# photodiodeAmplifier.net
KiCad netlist of a schematic drawn in Altium Designer
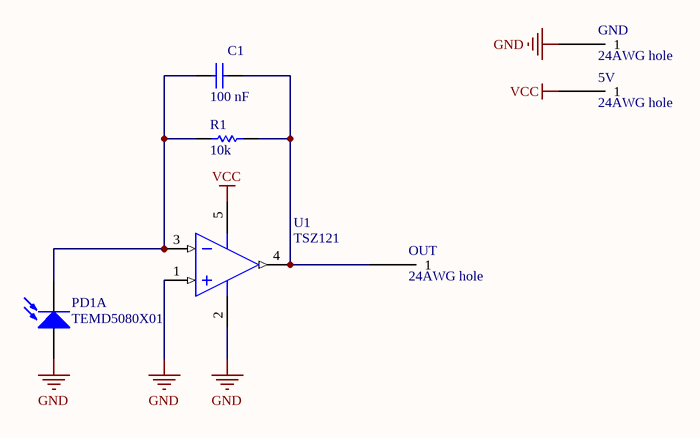
[diagram p0: photodiodeAmplifier.SchDoc]

(export (version "E")
  (design (tool "Eeschema 10.0.6"))
  (components
    (comp (ref "5V")
      (value "24AWG hole")
      (footprint "24AWG hole")
      (libsource (lib "AcqBoxLib") (part "24AWG hole"))
    )
    (comp (ref "C1") (value "100 nF") (footprint "CAP 0805") (libsource (lib "AcqBoxLib") (part "CAP 0805")))
    (comp (ref "GND")
      (value "24AWG hole")
      (footprint "24AWG hole")
      (libsource (lib "AcqBoxLib") (part "24AWG hole"))
    )
    (comp (ref "OUT")
      (value "24AWG hole")
      (footprint "24AWG hole")
      (libsource (lib "AcqBoxLib") (part "24AWG hole"))
    )
    (comp (ref "PD1")
      (value "TEMD5080X01")
      (footprint "Photodiode SMD PKG-1")
      (description "PIN Sillicium photodiode.")
      (libsource (lib "neigeMegaShieldLibrary") (part "TEMD5080X01"))
    )
    (comp (ref "R1")
      (value "10k")
      (footprint "RES 0805")
      (description "SMD Resistor 0805")
      (fields (field (name "Comment") "RES 0805"))
      (libsource (lib "AcqBoxLib") (part "RES 0805"))
    )
    (comp (ref "U1") (value "TSZ121") (footprint "SC-70-5") (libsource (lib "AcqBoxLib") (part "TSZ121")))
  )
  (nets
    (net (code "1") (name "GND") (class "Default")
      (node (ref "GND") (pin "1") (pinfunction "1_1") (pintype "passive"))
      (node (ref "PD1") (pin "1") (pinfunction "1_1") (pintype "passive"))
      (node (ref "U1") (pin "1") (pinfunction "INA+_1") (pintype "input"))
      (node (ref "U1") (pin "2") (pinfunction "V-_2") (pintype "power_in"))
    )
    (net (code "2") (name "Net-(U1-INA-)") (class "Default")
      (node (ref "C1") (pin "1") (pinfunction "1_1") (pintype "passive"))
      (node (ref "PD1") (pin "2") (pinfunction "2_2") (pintype "passive"))
      (node (ref "R1") (pin "1") (pinfunction "1_1") (pintype "passive"))
      (node (ref "U1") (pin "3") (pinfunction "INA-_3") (pintype "input"))
    )
    (net (code "3") (name "Net-(U1-OUTA)") (class "Default")
      (node (ref "C1") (pin "2") (pinfunction "2_2") (pintype "passive"))
      (node (ref "OUT") (pin "1") (pinfunction "1_1") (pintype "passive"))
      (node (ref "R1") (pin "2") (pinfunction "2_2") (pintype "passive"))
      (node (ref "U1") (pin "4") (pinfunction "OUTA_4") (pintype "output"))
    )
    (net (code "4") (name "VCC") (class "Default")
      (node (ref "5V") (pin "1") (pinfunction "1_1") (pintype "passive"))
      (node (ref "U1") (pin "5") (pinfunction "V+_5") (pintype "power_in"))
    )
  )
)
